# Interface_Board_V1_0.net
KiCad netlist of a schematic drawn in EAGLE
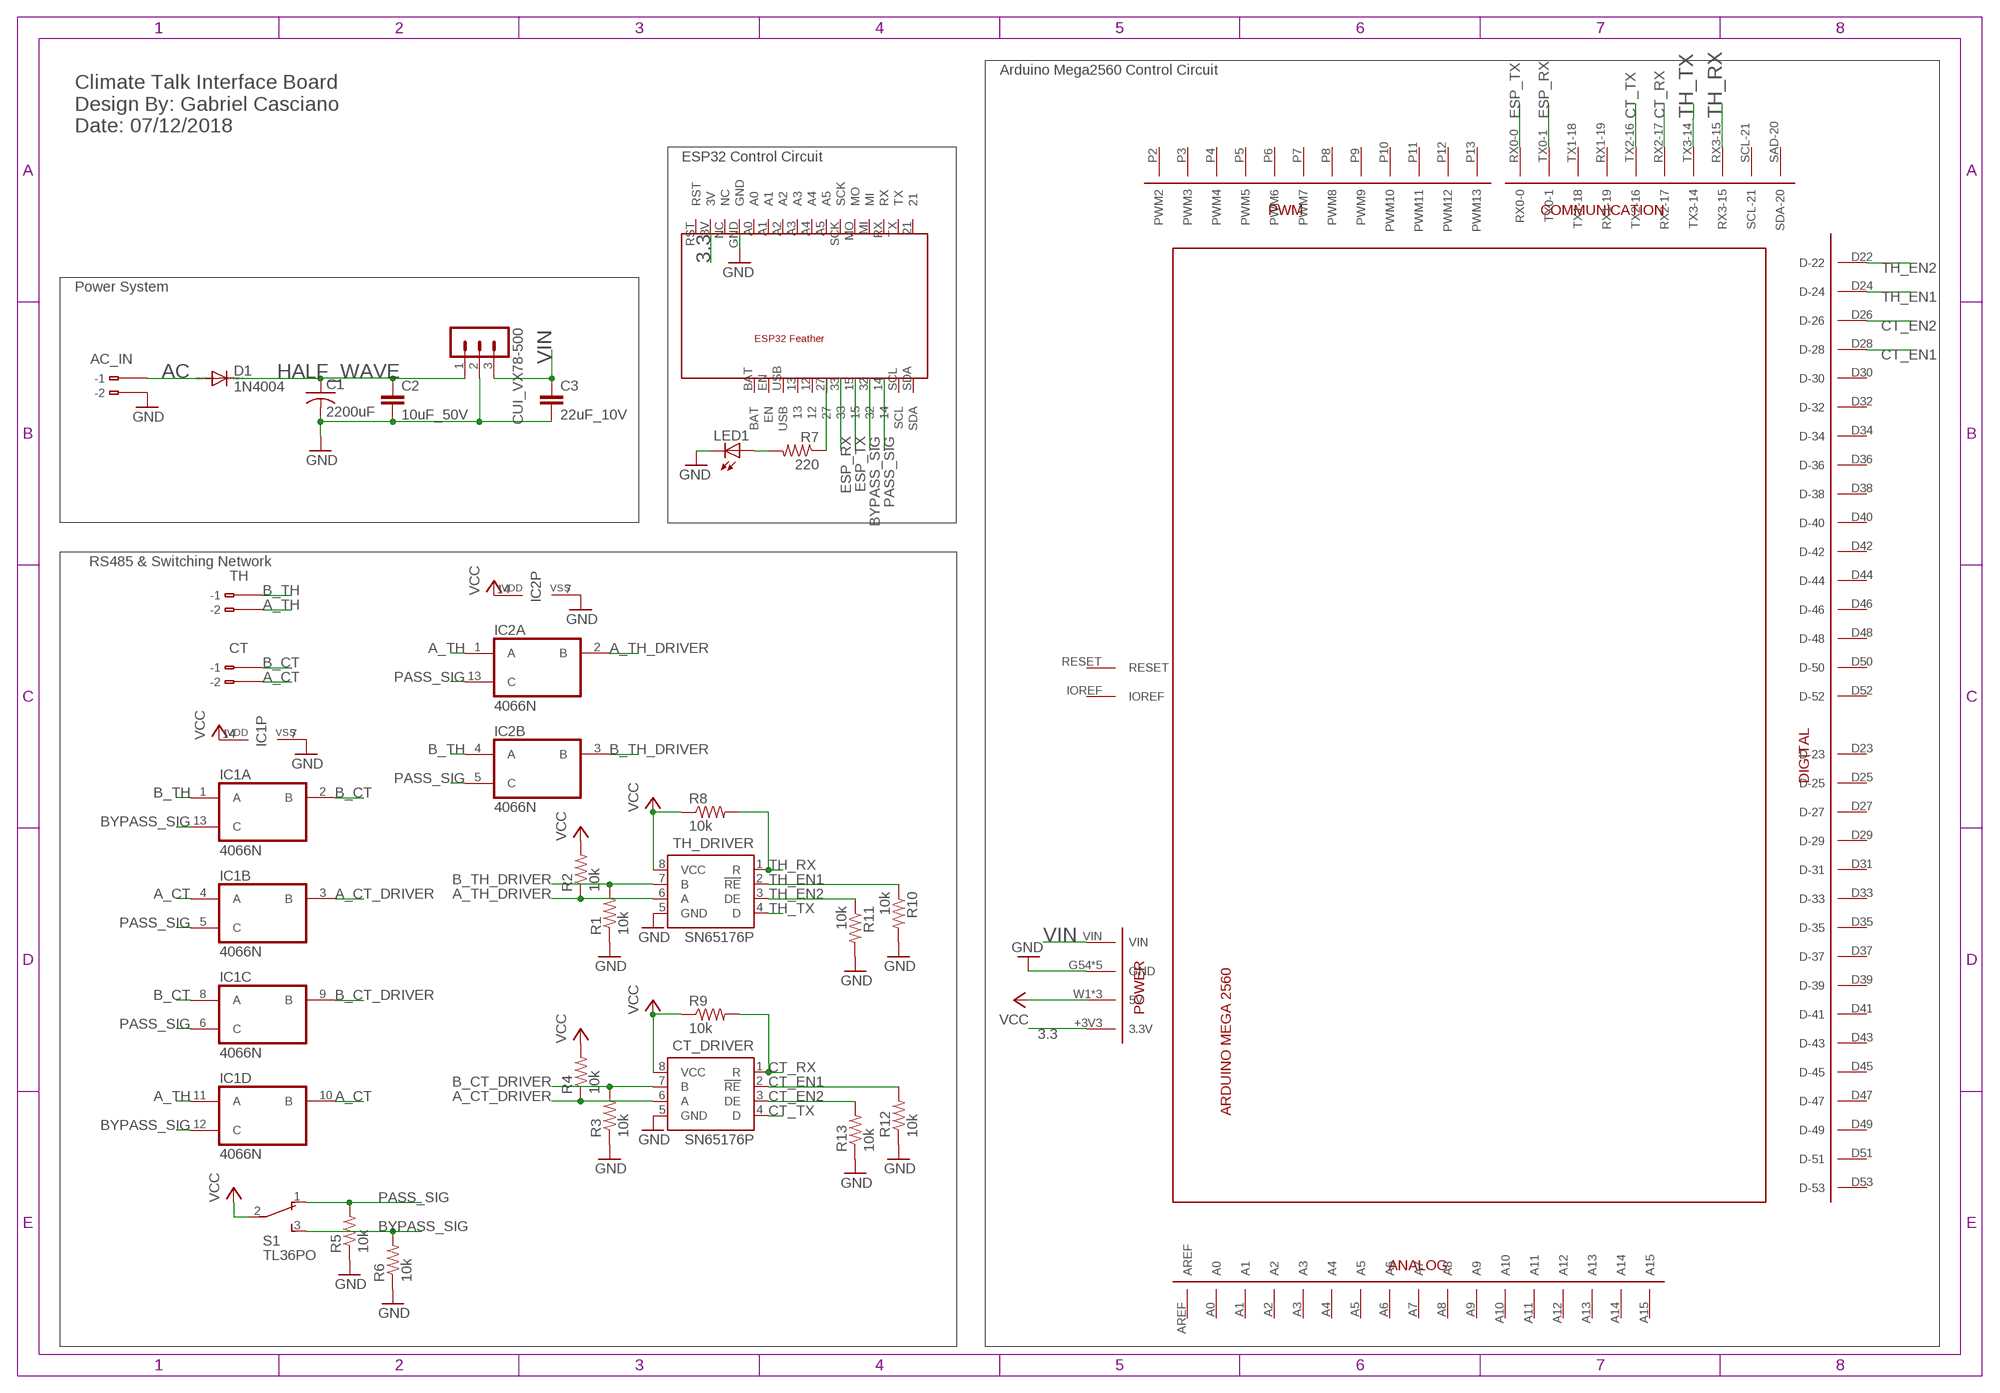
[diagram p0: schematic, sheet 1]

(export (version "E")
  (design (tool "Eeschema 10.0.6"))
  (components
    (comp (ref "AC_IN")
      (value "233-102")
      (footprint "eagle-import:233-102")
      (libsource (lib "eagle-import") (part "233-102"))
    )
    (comp (ref "C1")
      (value "2200uF")
      (footprint "eagle-import:C102-054X133")
      (libsource (lib "eagle-import") (part "C-US102-054X133"))
    )
    (comp (ref "C2")
      (value "10uF_50V")
      (footprint "eagle-import:C025-025X050")
      (libsource (lib "eagle-import") (part "C-EU025-025X050"))
    )
    (comp (ref "C3")
      (value "22uF_10V")
      (footprint "eagle-import:C025-025X050")
      (libsource (lib "eagle-import") (part "C-EU025-025X050"))
    )
    (comp (ref "CT")
      (value "233-102")
      (footprint "eagle-import:233-102")
      (libsource (lib "eagle-import") (part "233-102"))
    )
    (comp (ref "CT_DRIVER")
      (value "SN65176P")
      (footprint "eagle-import:DIL08")
      (fields (field (name "MF") "TEXAS INSTRUMENTS") (field (name "MPN") "SN65176BP"))
      (libsource (lib "eagle-import") (part "SN65176P"))
    )
    (comp (ref "CUI_VX78-500")
      (value "MA03-1")
      (footprint "eagle-import:MA03-1")
      (libsource (lib "eagle-import") (part "MA03-1"))
    )
    (comp (ref "D1")
      (value "1N4004")
      (footprint "eagle-import:DO41-10")
      (libsource (lib "eagle-import") (part "1N4004"))
    )
    (comp (ref "IC1")
      (value "4066N")
      (footprint "eagle-import:DIL14")
      (libsource (lib "eagle-import") (part "4066N"))
    )
    (comp (ref "IC2")
      (value "4066N")
      (footprint "eagle-import:DIL14")
      (libsource (lib "eagle-import") (part "4066N"))
    )
    (comp (ref "LED1")
      (value "LED5MM")
      (footprint "eagle-import:LED5MM")
      (libsource (lib "eagle-import") (part "LED5MM"))
    )
    (comp (ref "R1")
      (value "10k")
      (footprint "eagle-import:0204_7")
      (libsource (lib "eagle-import") (part "R-US_0204/7"))
    )
    (comp (ref "R2")
      (value "10k")
      (footprint "eagle-import:0204_7")
      (libsource (lib "eagle-import") (part "R-US_0204/7"))
    )
    (comp (ref "R3")
      (value "10k")
      (footprint "eagle-import:0204_7")
      (libsource (lib "eagle-import") (part "R-US_0204/7"))
    )
    (comp (ref "R4")
      (value "10k")
      (footprint "eagle-import:0204_7")
      (libsource (lib "eagle-import") (part "R-US_0204/7"))
    )
    (comp (ref "R5")
      (value "10k")
      (footprint "eagle-import:0204_7")
      (libsource (lib "eagle-import") (part "R-US_0204/7"))
    )
    (comp (ref "R6")
      (value "10k")
      (footprint "eagle-import:0204_7")
      (libsource (lib "eagle-import") (part "R-US_0204/7"))
    )
    (comp (ref "R7")
      (value "220")
      (footprint "eagle-import:0204_7")
      (libsource (lib "eagle-import") (part "R-US_0204/7"))
    )
    (comp (ref "R8")
      (value "10k")
      (footprint "eagle-import:0204_7")
      (libsource (lib "eagle-import") (part "R-US_0204/7"))
    )
    (comp (ref "R9")
      (value "10k")
      (footprint "eagle-import:0204_7")
      (libsource (lib "eagle-import") (part "R-US_0204/7"))
    )
    (comp (ref "R10")
      (value "10k")
      (footprint "eagle-import:0204_7")
      (libsource (lib "eagle-import") (part "R-US_0204/7"))
    )
    (comp (ref "R11")
      (value "10k")
      (footprint "eagle-import:0204_7")
      (libsource (lib "eagle-import") (part "R-US_0204/7"))
    )
    (comp (ref "R12")
      (value "10k")
      (footprint "eagle-import:0204_7")
      (libsource (lib "eagle-import") (part "R-US_0204/7"))
    )
    (comp (ref "R13")
      (value "10k")
      (footprint "eagle-import:0204_7")
      (libsource (lib "eagle-import") (part "R-US_0204/7"))
    )
    (comp (ref "S1")
      (value "TL36PO")
      (footprint "eagle-import:TL3XPO")
      (libsource (lib "eagle-import") (part "TL36PO"))
    )
    (comp (ref "S2")
      (value "ESP32")
      (footprint "eagle-import:ESP32")
      (libsource (lib "eagle-import") (part "ESP32"))
    )
    (comp (ref "TH")
      (value "233-102")
      (footprint "eagle-import:233-102")
      (libsource (lib "eagle-import") (part "233-102"))
    )
    (comp (ref "TH_DRIVER")
      (value "SN65176P")
      (footprint "eagle-import:DIL08")
      (fields (field (name "MF") "TEXAS INSTRUMENTS") (field (name "MPN") "SN65176BP"))
      (libsource (lib "eagle-import") (part "SN65176P"))
    )
    (comp (ref "U$1")
      (value "BOARD_ARDUINO-MEGA")
      (footprint "eagle-import:BOARD_ARDUINO_MEGA")
      (libsource (lib "eagle-import") (part "BOARD_ARDUINO-MEGA"))
    )
  )
  (nets
    (net (code "1") (name "/3.3") (class "Default")
      (node (ref "S2") (pin "3V") (pinfunction "3V_3V") (pintype "bidirectional"))
      (node (ref "U$1") (pin "+3V3") (pinfunction "3.3V_+3V3") (pintype "power_in"))
    )
    (net (code "2") (name "/AC") (class "Default")
      (node (ref "AC_IN") (pin "B1") (pinfunction "B-1_B1") (pintype "passive"))
      (node (ref "D1") (pin "A") (pinfunction "A_A") (pintype "passive"))
    )
    (net (code "3") (name "/A_CT") (class "Default")
      (node (ref "CT") (pin "B2") (pinfunction "B-2_B2") (pintype "passive"))
      (node (ref "IC1") (pin "10") (pinfunction "B_10") (pintype "tri_state"))
      (node (ref "IC1") (pin "4") (pinfunction "A_4") (pintype "tri_state"))
    )
    (net (code "4") (name "/A_CT_DRIVER") (class "Default")
      (node (ref "CT_DRIVER") (pin "6") (pinfunction "A_6") (pintype "input"))
      (node (ref "IC1") (pin "3") (pinfunction "B_3") (pintype "tri_state"))
      (node (ref "R4") (pin "1") (pinfunction "1_1") (pintype "passive"))
    )
    (net (code "5") (name "/A_TH") (class "Default")
      (node (ref "IC1") (pin "11") (pinfunction "A_11") (pintype "tri_state"))
      (node (ref "IC2") (pin "1") (pinfunction "A_1") (pintype "tri_state"))
      (node (ref "TH") (pin "B2") (pinfunction "B-2_B2") (pintype "passive"))
    )
    (net (code "6") (name "/A_TH_DRIVER") (class "Default")
      (node (ref "IC2") (pin "2") (pinfunction "B_2") (pintype "tri_state"))
      (node (ref "R2") (pin "1") (pinfunction "1_1") (pintype "passive"))
      (node (ref "TH_DRIVER") (pin "6") (pinfunction "A_6") (pintype "input"))
    )
    (net (code "7") (name "/BYPASS_SIG") (class "Default")
      (node (ref "IC1") (pin "12") (pinfunction "C_12") (pintype "input"))
      (node (ref "IC1") (pin "13") (pinfunction "C_13") (pintype "input"))
      (node (ref "R6") (pin "2") (pinfunction "2_2") (pintype "passive"))
      (node (ref "S1") (pin "3") (pinfunction "S_3") (pintype "passive"))
      (node (ref "S2") (pin "32") (pinfunction "32_32") (pintype "bidirectional"))
    )
    (net (code "8") (name "/B_CT") (class "Default")
      (node (ref "CT") (pin "B1") (pinfunction "B-1_B1") (pintype "passive"))
      (node (ref "IC1") (pin "2") (pinfunction "B_2") (pintype "tri_state"))
      (node (ref "IC1") (pin "8") (pinfunction "A_8") (pintype "tri_state"))
    )
    (net (code "9") (name "/B_CT_DRIVER") (class "Default")
      (node (ref "CT_DRIVER") (pin "7") (pinfunction "B_7") (pintype "input"))
      (node (ref "IC1") (pin "9") (pinfunction "B_9") (pintype "tri_state"))
      (node (ref "R3") (pin "2") (pinfunction "2_2") (pintype "passive"))
    )
    (net (code "10") (name "/B_TH") (class "Default")
      (node (ref "IC1") (pin "1") (pinfunction "A_1") (pintype "tri_state"))
      (node (ref "IC2") (pin "4") (pinfunction "A_4") (pintype "tri_state"))
      (node (ref "TH") (pin "B1") (pinfunction "B-1_B1") (pintype "passive"))
    )
    (net (code "11") (name "/B_TH_DRIVER") (class "Default")
      (node (ref "IC2") (pin "3") (pinfunction "B_3") (pintype "tri_state"))
      (node (ref "R1") (pin "2") (pinfunction "2_2") (pintype "passive"))
      (node (ref "TH_DRIVER") (pin "7") (pinfunction "B_7") (pintype "input"))
    )
    (net (code "12") (name "/CT_EN1") (class "Default")
      (node (ref "CT_DRIVER") (pin "2") (pinfunction "~{RE}_2") (pintype "input"))
      (node (ref "R12") (pin "2") (pinfunction "2_2") (pintype "passive"))
      (node (ref "U$1") (pin "D28") (pinfunction "D-28_D28") (pintype "bidirectional"))
    )
    (net (code "13") (name "/CT_EN2") (class "Default")
      (node (ref "CT_DRIVER") (pin "3") (pinfunction "DE_3") (pintype "input"))
      (node (ref "R13") (pin "2") (pinfunction "2_2") (pintype "passive"))
      (node (ref "U$1") (pin "D26") (pinfunction "D-26_D26") (pintype "bidirectional"))
    )
    (net (code "14") (name "/CT_RX") (class "Default")
      (node (ref "CT_DRIVER") (pin "1") (pinfunction "R_1") (pintype "input"))
      (node (ref "R9") (pin "2") (pinfunction "2_2") (pintype "passive"))
      (node (ref "U$1") (pin "RX2-17") (pinfunction "RX2-17_RX2-17") (pintype "bidirectional"))
    )
    (net (code "15") (name "/CT_TX") (class "Default")
      (node (ref "CT_DRIVER") (pin "4") (pinfunction "D_4") (pintype "input"))
      (node (ref "U$1") (pin "TX2-16") (pinfunction "TX2-16_TX2-16") (pintype "bidirectional"))
    )
    (net (code "16") (name "/ESP_RX") (class "Default")
      (node (ref "S2") (pin "33") (pinfunction "33_33") (pintype "bidirectional"))
      (node (ref "U$1") (pin "TX0-1") (pinfunction "TX0-1_TX0-1") (pintype "bidirectional"))
    )
    (net (code "17") (name "/ESP_TX") (class "Default")
      (node (ref "S2") (pin "15") (pinfunction "15_15") (pintype "bidirectional"))
      (node (ref "U$1") (pin "RX0-0") (pinfunction "RX0-0_RX0-0") (pintype "bidirectional"))
    )
    (net (code "18") (name "/HALF_WAVE") (class "Default")
      (node (ref "C1") (pin "1") (pinfunction "1_1") (pintype "passive"))
      (node (ref "C2") (pin "1") (pinfunction "1_1") (pintype "passive"))
      (node (ref "CUI_VX78-500") (pin "1") (pinfunction "1_1") (pintype "passive"))
      (node (ref "D1") (pin "C") (pinfunction "C_C") (pintype "passive"))
    )
    (net (code "19") (name "/PASS_SIG") (class "Default")
      (node (ref "IC1") (pin "5") (pinfunction "C_5") (pintype "input"))
      (node (ref "IC1") (pin "6") (pinfunction "C_6") (pintype "input"))
      (node (ref "IC2") (pin "13") (pinfunction "C_13") (pintype "input"))
      (node (ref "IC2") (pin "5") (pinfunction "C_5") (pintype "input"))
      (node (ref "R5") (pin "2") (pinfunction "2_2") (pintype "passive"))
      (node (ref "S1") (pin "1") (pinfunction "O_1") (pintype "passive"))
      (node (ref "S2") (pin "14") (pinfunction "14_14") (pintype "bidirectional"))
    )
    (net (code "20") (name "/TH_EN1") (class "Default")
      (node (ref "R10") (pin "1") (pinfunction "1_1") (pintype "passive"))
      (node (ref "TH_DRIVER") (pin "2") (pinfunction "~{RE}_2") (pintype "input"))
      (node (ref "U$1") (pin "D24") (pinfunction "D-24_D24") (pintype "bidirectional"))
    )
    (net (code "21") (name "/TH_EN2") (class "Default")
      (node (ref "R11") (pin "1") (pinfunction "1_1") (pintype "passive"))
      (node (ref "TH_DRIVER") (pin "3") (pinfunction "DE_3") (pintype "input"))
      (node (ref "U$1") (pin "D22") (pinfunction "D-22_D22") (pintype "bidirectional"))
    )
    (net (code "22") (name "/TH_RX") (class "Default")
      (node (ref "R8") (pin "2") (pinfunction "2_2") (pintype "passive"))
      (node (ref "TH_DRIVER") (pin "1") (pinfunction "R_1") (pintype "input"))
      (node (ref "U$1") (pin "RX3-15") (pinfunction "RX3-15_RX3-15") (pintype "bidirectional"))
    )
    (net (code "23") (name "/TH_TX") (class "Default")
      (node (ref "TH_DRIVER") (pin "4") (pinfunction "D_4") (pintype "input"))
      (node (ref "U$1") (pin "TX3-14") (pinfunction "TX3-14_TX3-14") (pintype "bidirectional"))
    )
    (net (code "24") (name "/VIN") (class "Default")
      (node (ref "C3") (pin "1") (pinfunction "1_1") (pintype "passive"))
      (node (ref "CUI_VX78-500") (pin "3") (pinfunction "3_3") (pintype "passive"))
      (node (ref "U$1") (pin "VIN") (pinfunction "VIN_VIN") (pintype "power_in"))
    )
    (net (code "25") (name "GND") (class "Default")
      (node (ref "AC_IN") (pin "B2") (pinfunction "B-2_B2") (pintype "passive"))
      (node (ref "C1") (pin "2") (pinfunction "2_2") (pintype "passive"))
      (node (ref "C2") (pin "2") (pinfunction "2_2") (pintype "passive"))
      (node (ref "C3") (pin "2") (pinfunction "2_2") (pintype "passive"))
      (node (ref "CT_DRIVER") (pin "5") (pinfunction "GND_5") (pintype "input"))
      (node (ref "CUI_VX78-500") (pin "2") (pinfunction "2_2") (pintype "passive"))
      (node (ref "IC1") (pin "7") (pinfunction "VSS_7") (pintype "power_in"))
      (node (ref "IC2") (pin "7") (pinfunction "VSS_7") (pintype "power_in"))
      (node (ref "LED1") (pin "K") (pinfunction "C_K") (pintype "passive"))
      (node (ref "R1") (pin "1") (pinfunction "1_1") (pintype "passive"))
      (node (ref "R10") (pin "2") (pinfunction "2_2") (pintype "passive"))
      (node (ref "R11") (pin "2") (pinfunction "2_2") (pintype "passive"))
      (node (ref "R12") (pin "1") (pinfunction "1_1") (pintype "passive"))
      (node (ref "R13") (pin "1") (pinfunction "1_1") (pintype "passive"))
      (node (ref "R3") (pin "1") (pinfunction "1_1") (pintype "passive"))
      (node (ref "R5") (pin "1") (pinfunction "1_1") (pintype "passive"))
      (node (ref "R6") (pin "1") (pinfunction "1_1") (pintype "passive"))
      (node (ref "S2") (pin "GND") (pinfunction "GND_GND") (pintype "bidirectional"))
      (node (ref "TH_DRIVER") (pin "5") (pinfunction "GND_5") (pintype "input"))
      (node (ref "U$1") (pin "G54") (pinfunction "GND_G54") (pintype "power_in"))
      (node (ref "U$1") (pin "G55") (pinfunction "GND_G55") (pintype "power_in"))
      (node (ref "U$1") (pin "G56") (pinfunction "GND_G56") (pintype "power_in"))
      (node (ref "U$1") (pin "G57") (pinfunction "GND_G57") (pintype "power_in"))
      (node (ref "U$1") (pin "G58") (pinfunction "GND_G58") (pintype "power_in"))
    )
    (net (code "26") (name "Net-(LED1-PadA)") (class "Default")
      (node (ref "LED1") (pin "A") (pinfunction "A_A") (pintype "passive"))
      (node (ref "R7") (pin "2") (pinfunction "2_2") (pintype "passive"))
    )
    (net (code "27") (name "Net-(R7-Pad1)") (class "Default")
      (node (ref "R7") (pin "1") (pinfunction "1_1") (pintype "passive"))
      (node (ref "S2") (pin "27") (pinfunction "27_27") (pintype "bidirectional"))
    )
    (net (code "28") (name "VCC") (class "Default")
      (node (ref "CT_DRIVER") (pin "8") (pinfunction "VCC_8") (pintype "input"))
      (node (ref "IC1") (pin "14") (pinfunction "VDD_14") (pintype "power_in"))
      (node (ref "IC2") (pin "14") (pinfunction "VDD_14") (pintype "power_in"))
      (node (ref "R2") (pin "2") (pinfunction "2_2") (pintype "passive"))
      (node (ref "R4") (pin "2") (pinfunction "2_2") (pintype "passive"))
      (node (ref "R8") (pin "1") (pinfunction "1_1") (pintype "passive"))
      (node (ref "R9") (pin "1") (pinfunction "1_1") (pintype "passive"))
      (node (ref "S1") (pin "2") (pinfunction "P_2") (pintype "passive"))
      (node (ref "TH_DRIVER") (pin "8") (pinfunction "VCC_8") (pintype "input"))
      (node (ref "U$1") (pin "W1") (pinfunction "5V_W1") (pintype "power_in"))
      (node (ref "U$1") (pin "W2") (pinfunction "5V_W2") (pintype "power_in"))
      (node (ref "U$1") (pin "W3") (pinfunction "5V_W3") (pintype "power_in"))
    )
    (net (code "29") (name "unconnected-(AC_IN--1-PadA1)") (class "Default")
      (node (ref "AC_IN") (pin "A1") (pinfunction "-1_A1") (pintype "passive"))
    )
    (net (code "30") (name "unconnected-(AC_IN--2-PadA2)") (class "Default")
      (node (ref "AC_IN") (pin "A2") (pinfunction "-2_A2") (pintype "passive"))
    )
    (net (code "31") (name "unconnected-(CT--1-PadA1)") (class "Default")
      (node (ref "CT") (pin "A1") (pinfunction "-1_A1") (pintype "passive"))
    )
    (net (code "32") (name "unconnected-(CT--2-PadA2)") (class "Default")
      (node (ref "CT") (pin "A2") (pinfunction "-2_A2") (pintype "passive"))
    )
    (net (code "33") (name "unconnected-(S2-Pad12)") (class "Default")
      (node (ref "S2") (pin "12") (pinfunction "12_12") (pintype "bidirectional"))
    )
    (net (code "34") (name "unconnected-(S2-Pad13)") (class "Default")
      (node (ref "S2") (pin "13") (pinfunction "13_13") (pintype "bidirectional"))
    )
    (net (code "35") (name "unconnected-(S2-Pad21)") (class "Default")
      (node (ref "S2") (pin "21") (pinfunction "21_21") (pintype "bidirectional"))
    )
    (net (code "36") (name "unconnected-(S2-PadA0)") (class "Default")
      (node (ref "S2") (pin "A0") (pinfunction "A0_A0") (pintype "bidirectional"))
    )
    (net (code "37") (name "unconnected-(S2-PadA1)") (class "Default")
      (node (ref "S2") (pin "A1") (pinfunction "A1_A1") (pintype "bidirectional"))
    )
    (net (code "38") (name "unconnected-(S2-PadA2)") (class "Default")
      (node (ref "S2") (pin "A2") (pinfunction "A2_A2") (pintype "bidirectional"))
    )
    (net (code "39") (name "unconnected-(S2-PadA3)") (class "Default")
      (node (ref "S2") (pin "A3") (pinfunction "A3_A3") (pintype "bidirectional"))
    )
    (net (code "40") (name "unconnected-(S2-PadA4)") (class "Default")
      (node (ref "S2") (pin "A4") (pinfunction "A4_A4") (pintype "bidirectional"))
    )
    (net (code "41") (name "unconnected-(S2-PadA5)") (class "Default")
      (node (ref "S2") (pin "A5") (pinfunction "A5_A5") (pintype "bidirectional"))
    )
    (net (code "42") (name "unconnected-(S2-PadBAT)") (class "Default")
      (node (ref "S2") (pin "BAT") (pinfunction "BAT_BAT") (pintype "bidirectional"))
    )
    (net (code "43") (name "unconnected-(S2-PadEN)") (class "Default")
      (node (ref "S2") (pin "EN") (pinfunction "EN_EN") (pintype "bidirectional"))
    )
    (net (code "44") (name "unconnected-(S2-PadMI)") (class "Default")
      (node (ref "S2") (pin "MI") (pinfunction "MI_MI") (pintype "bidirectional"))
    )
    (net (code "45") (name "unconnected-(S2-PadMO)") (class "Default")
      (node (ref "S2") (pin "MO") (pinfunction "MO_MO") (pintype "bidirectional"))
    )
    (net (code "46") (name "unconnected-(S2-PadNC)") (class "Default")
      (node (ref "S2") (pin "NC") (pinfunction "NC_NC") (pintype "bidirectional"))
    )
    (net (code "47") (name "unconnected-(S2-PadRST)") (class "Default")
      (node (ref "S2") (pin "RST") (pinfunction "RST_RST") (pintype "bidirectional"))
    )
    (net (code "48") (name "unconnected-(S2-PadRX)") (class "Default")
      (node (ref "S2") (pin "RX") (pinfunction "RX_RX") (pintype "bidirectional"))
    )
    (net (code "49") (name "unconnected-(S2-PadSCK)") (class "Default")
      (node (ref "S2") (pin "SCK") (pinfunction "SCK_SCK") (pintype "bidirectional"))
    )
    (net (code "50") (name "unconnected-(S2-PadSCL)") (class "Default")
      (node (ref "S2") (pin "SCL") (pinfunction "SCL_SCL") (pintype "bidirectional"))
    )
    (net (code "51") (name "unconnected-(S2-PadSDA)") (class "Default")
      (node (ref "S2") (pin "SDA") (pinfunction "SDA_SDA") (pintype "bidirectional"))
    )
    (net (code "52") (name "unconnected-(S2-PadTX)") (class "Default")
      (node (ref "S2") (pin "TX") (pinfunction "TX_TX") (pintype "bidirectional"))
    )
    (net (code "53") (name "unconnected-(S2-PadUSB)") (class "Default")
      (node (ref "S2") (pin "USB") (pinfunction "USB_USB") (pintype "bidirectional"))
    )
    (net (code "54") (name "unconnected-(TH--1-PadA1)") (class "Default")
      (node (ref "TH") (pin "A1") (pinfunction "-1_A1") (pintype "passive"))
    )
    (net (code "55") (name "unconnected-(TH--2-PadA2)") (class "Default")
      (node (ref "TH") (pin "A2") (pinfunction "-2_A2") (pintype "passive"))
    )
    (net (code "56") (name "unconnected-(U$1-D-23-PadD23)") (class "Default")
      (node (ref "U$1") (pin "D23") (pinfunction "D-23_D23") (pintype "bidirectional"))
    )
    (net (code "57") (name "unconnected-(U$1-D-25-PadD25)") (class "Default")
      (node (ref "U$1") (pin "D25") (pinfunction "D-25_D25") (pintype "bidirectional"))
    )
    (net (code "58") (name "unconnected-(U$1-D-27-PadD27)") (class "Default")
      (node (ref "U$1") (pin "D27") (pinfunction "D-27_D27") (pintype "bidirectional"))
    )
    (net (code "59") (name "unconnected-(U$1-D-29-PadD29)") (class "Default")
      (node (ref "U$1") (pin "D29") (pinfunction "D-29_D29") (pintype "bidirectional"))
    )
    (net (code "60") (name "unconnected-(U$1-D-30-PadD30)") (class "Default")
      (node (ref "U$1") (pin "D30") (pinfunction "D-30_D30") (pintype "bidirectional"))
    )
    (net (code "61") (name "unconnected-(U$1-D-31-PadD31)") (class "Default")
      (node (ref "U$1") (pin "D31") (pinfunction "D-31_D31") (pintype "bidirectional"))
    )
    (net (code "62") (name "unconnected-(U$1-D-32-PadD32)") (class "Default")
      (node (ref "U$1") (pin "D32") (pinfunction "D-32_D32") (pintype "bidirectional"))
    )
    (net (code "63") (name "unconnected-(U$1-D-33-PadD33)") (class "Default")
      (node (ref "U$1") (pin "D33") (pinfunction "D-33_D33") (pintype "bidirectional"))
    )
    (net (code "64") (name "unconnected-(U$1-D-34-PadD34)") (class "Default")
      (node (ref "U$1") (pin "D34") (pinfunction "D-34_D34") (pintype "bidirectional"))
    )
    (net (code "65") (name "unconnected-(U$1-D-35-PadD35)") (class "Default")
      (node (ref "U$1") (pin "D35") (pinfunction "D-35_D35") (pintype "bidirectional"))
    )
    (net (code "66") (name "unconnected-(U$1-D-36-PadD36)") (class "Default")
      (node (ref "U$1") (pin "D36") (pinfunction "D-36_D36") (pintype "bidirectional"))
    )
    (net (code "67") (name "unconnected-(U$1-D-37-PadD37)") (class "Default")
      (node (ref "U$1") (pin "D37") (pinfunction "D-37_D37") (pintype "bidirectional"))
    )
    (net (code "68") (name "unconnected-(U$1-D-38-PadD38)") (class "Default")
      (node (ref "U$1") (pin "D38") (pinfunction "D-38_D38") (pintype "bidirectional"))
    )
    (net (code "69") (name "unconnected-(U$1-D-39-PadD39)") (class "Default")
      (node (ref "U$1") (pin "D39") (pinfunction "D-39_D39") (pintype "bidirectional"))
    )
    (net (code "70") (name "unconnected-(U$1-D-40-PadD40)") (class "Default")
      (node (ref "U$1") (pin "D40") (pinfunction "D-40_D40") (pintype "bidirectional"))
    )
    (net (code "71") (name "unconnected-(U$1-D-41-PadD41)") (class "Default")
      (node (ref "U$1") (pin "D41") (pinfunction "D-41_D41") (pintype "bidirectional"))
    )
    (net (code "72") (name "unconnected-(U$1-D-42-PadD42)") (class "Default")
      (node (ref "U$1") (pin "D42") (pinfunction "D-42_D42") (pintype "bidirectional"))
    )
    (net (code "73") (name "unconnected-(U$1-D-43-PadD43)") (class "Default")
      (node (ref "U$1") (pin "D43") (pinfunction "D-43_D43") (pintype "bidirectional"))
    )
    (net (code "74") (name "unconnected-(U$1-D-44-PadD44)") (class "Default")
      (node (ref "U$1") (pin "D44") (pinfunction "D-44_D44") (pintype "bidirectional"))
    )
    (net (code "75") (name "unconnected-(U$1-D-45-PadD45)") (class "Default")
      (node (ref "U$1") (pin "D45") (pinfunction "D-45_D45") (pintype "bidirectional"))
    )
    (net (code "76") (name "unconnected-(U$1-D-46-PadD46)") (class "Default")
      (node (ref "U$1") (pin "D46") (pinfunction "D-46_D46") (pintype "bidirectional"))
    )
    (net (code "77") (name "unconnected-(U$1-D-47-PadD47)") (class "Default")
      (node (ref "U$1") (pin "D47") (pinfunction "D-47_D47") (pintype "bidirectional"))
    )
    (net (code "78") (name "unconnected-(U$1-D-48-PadD48)") (class "Default")
      (node (ref "U$1") (pin "D48") (pinfunction "D-48_D48") (pintype "bidirectional"))
    )
    (net (code "79") (name "unconnected-(U$1-D-49-PadD49)") (class "Default")
      (node (ref "U$1") (pin "D49") (pinfunction "D-49_D49") (pintype "bidirectional"))
    )
    (net (code "80") (name "unconnected-(U$1-D-50-PadD50)") (class "Default")
      (node (ref "U$1") (pin "D50") (pinfunction "D-50_D50") (pintype "bidirectional"))
    )
    (net (code "81") (name "unconnected-(U$1-D-51-PadD51)") (class "Default")
      (node (ref "U$1") (pin "D51") (pinfunction "D-51_D51") (pintype "bidirectional"))
    )
    (net (code "82") (name "unconnected-(U$1-D-52-PadD52)") (class "Default")
      (node (ref "U$1") (pin "D52") (pinfunction "D-52_D52") (pintype "bidirectional"))
    )
    (net (code "83") (name "unconnected-(U$1-D-53-PadD53)") (class "Default")
      (node (ref "U$1") (pin "D53") (pinfunction "D-53_D53") (pintype "bidirectional"))
    )
    (net (code "84") (name "unconnected-(U$1-PWM2-PadP2)") (class "Default")
      (node (ref "U$1") (pin "P2") (pinfunction "PWM2_P2") (pintype "bidirectional"))
    )
    (net (code "85") (name "unconnected-(U$1-PWM3-PadP3)") (class "Default")
      (node (ref "U$1") (pin "P3") (pinfunction "PWM3_P3") (pintype "bidirectional"))
    )
    (net (code "86") (name "unconnected-(U$1-PWM4-PadP4)") (class "Default")
      (node (ref "U$1") (pin "P4") (pinfunction "PWM4_P4") (pintype "bidirectional"))
    )
    (net (code "87") (name "unconnected-(U$1-PWM5-PadP5)") (class "Default")
      (node (ref "U$1") (pin "P5") (pinfunction "PWM5_P5") (pintype "bidirectional"))
    )
    (net (code "88") (name "unconnected-(U$1-PWM6-PadP6)") (class "Default")
      (node (ref "U$1") (pin "P6") (pinfunction "PWM6_P6") (pintype "bidirectional"))
    )
    (net (code "89") (name "unconnected-(U$1-PWM7-PadP7)") (class "Default")
      (node (ref "U$1") (pin "P7") (pinfunction "PWM7_P7") (pintype "bidirectional"))
    )
    (net (code "90") (name "unconnected-(U$1-PWM8-PadP8)") (class "Default")
      (node (ref "U$1") (pin "P8") (pinfunction "PWM8_P8") (pintype "bidirectional"))
    )
    (net (code "91") (name "unconnected-(U$1-PWM9-PadP9)") (class "Default")
      (node (ref "U$1") (pin "P9") (pinfunction "PWM9_P9") (pintype "bidirectional"))
    )
    (net (code "92") (name "unconnected-(U$1-PWM10-PadP10)") (class "Default")
      (node (ref "U$1") (pin "P10") (pinfunction "PWM10_P10") (pintype "bidirectional"))
    )
    (net (code "93") (name "unconnected-(U$1-PWM11-PadP11)") (class "Default")
      (node (ref "U$1") (pin "P11") (pinfunction "PWM11_P11") (pintype "bidirectional"))
    )
    (net (code "94") (name "unconnected-(U$1-PWM12-PadP12)") (class "Default")
      (node (ref "U$1") (pin "P12") (pinfunction "PWM12_P12") (pintype "bidirectional"))
    )
    (net (code "95") (name "unconnected-(U$1-PWM13-PadP13)") (class "Default")
      (node (ref "U$1") (pin "P13") (pinfunction "PWM13_P13") (pintype "bidirectional"))
    )
    (net (code "96") (name "unconnected-(U$1-PadA0)") (class "Default")
      (node (ref "U$1") (pin "A0") (pinfunction "A0_A0") (pintype "bidirectional"))
    )
    (net (code "97") (name "unconnected-(U$1-PadA1)") (class "Default")
      (node (ref "U$1") (pin "A1") (pinfunction "A1_A1") (pintype "bidirectional"))
    )
    (net (code "98") (name "unconnected-(U$1-PadA2)") (class "Default")
      (node (ref "U$1") (pin "A2") (pinfunction "A2_A2") (pintype "bidirectional"))
    )
    (net (code "99") (name "unconnected-(U$1-PadA3)") (class "Default")
      (node (ref "U$1") (pin "A3") (pinfunction "A3_A3") (pintype "bidirectional"))
    )
    (net (code "100") (name "unconnected-(U$1-PadA4)") (class "Default")
      (node (ref "U$1") (pin "A4") (pinfunction "A4_A4") (pintype "bidirectional"))
    )
    (net (code "101") (name "unconnected-(U$1-PadA5)") (class "Default")
      (node (ref "U$1") (pin "A5") (pinfunction "A5_A5") (pintype "bidirectional"))
    )
    (net (code "102") (name "unconnected-(U$1-PadA6)") (class "Default")
      (node (ref "U$1") (pin "A6") (pinfunction "A6_A6") (pintype "bidirectional"))
    )
    (net (code "103") (name "unconnected-(U$1-PadA7)") (class "Default")
      (node (ref "U$1") (pin "A7") (pinfunction "A7_A7") (pintype "bidirectional"))
    )
    (net (code "104") (name "unconnected-(U$1-PadA8)") (class "Default")
      (node (ref "U$1") (pin "A8") (pinfunction "A8_A8") (pintype "bidirectional"))
    )
    (net (code "105") (name "unconnected-(U$1-PadA9)") (class "Default")
      (node (ref "U$1") (pin "A9") (pinfunction "A9_A9") (pintype "bidirectional"))
    )
    (net (code "106") (name "unconnected-(U$1-PadA10)") (class "Default")
      (node (ref "U$1") (pin "A10") (pinfunction "A10_A10") (pintype "bidirectional"))
    )
    (net (code "107") (name "unconnected-(U$1-PadA11)") (class "Default")
      (node (ref "U$1") (pin "A11") (pinfunction "A11_A11") (pintype "bidirectional"))
    )
    (net (code "108") (name "unconnected-(U$1-PadA12)") (class "Default")
      (node (ref "U$1") (pin "A12") (pinfunction "A12_A12") (pintype "bidirectional"))
    )
    (net (code "109") (name "unconnected-(U$1-PadA13)") (class "Default")
      (node (ref "U$1") (pin "A13") (pinfunction "A13_A13") (pintype "bidirectional"))
    )
    (net (code "110") (name "unconnected-(U$1-PadA14)") (class "Default")
      (node (ref "U$1") (pin "A14") (pinfunction "A14_A14") (pintype "bidirectional"))
    )
    (net (code "111") (name "unconnected-(U$1-PadA15)") (class "Default")
      (node (ref "U$1") (pin "A15") (pinfunction "A15_A15") (pintype "bidirectional"))
    )
    (net (code "112") (name "unconnected-(U$1-PadAREF)") (class "Default")
      (node (ref "U$1") (pin "AREF") (pinfunction "AREF_AREF") (pintype "bidirectional"))
    )
    (net (code "113") (name "unconnected-(U$1-PadIOREF)") (class "Default")
      (node (ref "U$1") (pin "IOREF") (pinfunction "IOREF_IOREF") (pintype "bidirectional"))
    )
    (net (code "114") (name "unconnected-(U$1-PadRESET)") (class "Default")
      (node (ref "U$1") (pin "RESET") (pinfunction "RESET_RESET") (pintype "bidirectional"))
    )
    (net (code "115") (name "unconnected-(U$1-PadRX1-19)") (class "Default")
      (node (ref "U$1") (pin "RX1-19") (pinfunction "RX1-19_RX1-19") (pintype "bidirectional"))
    )
    (net (code "116") (name "unconnected-(U$1-PadSCL-21)") (class "Default")
      (node (ref "U$1") (pin "SCL-21") (pinfunction "SCL-21_SCL-21") (pintype "bidirectional"))
    )
    (net (code "117") (name "unconnected-(U$1-PadTX1-18)") (class "Default")
      (node (ref "U$1") (pin "TX1-18") (pinfunction "TX1-18_TX1-18") (pintype "bidirectional"))
    )
    (net (code "118") (name "unconnected-(U$1-SDA-20-PadSAD-20)") (class "Default")
      (node (ref "U$1") (pin "SAD-20") (pinfunction "SDA-20_SAD-20") (pintype "bidirectional"))
    )
  )
)
